# Communication.net
KiCad netlist of a schematic drawn in Altium Designer
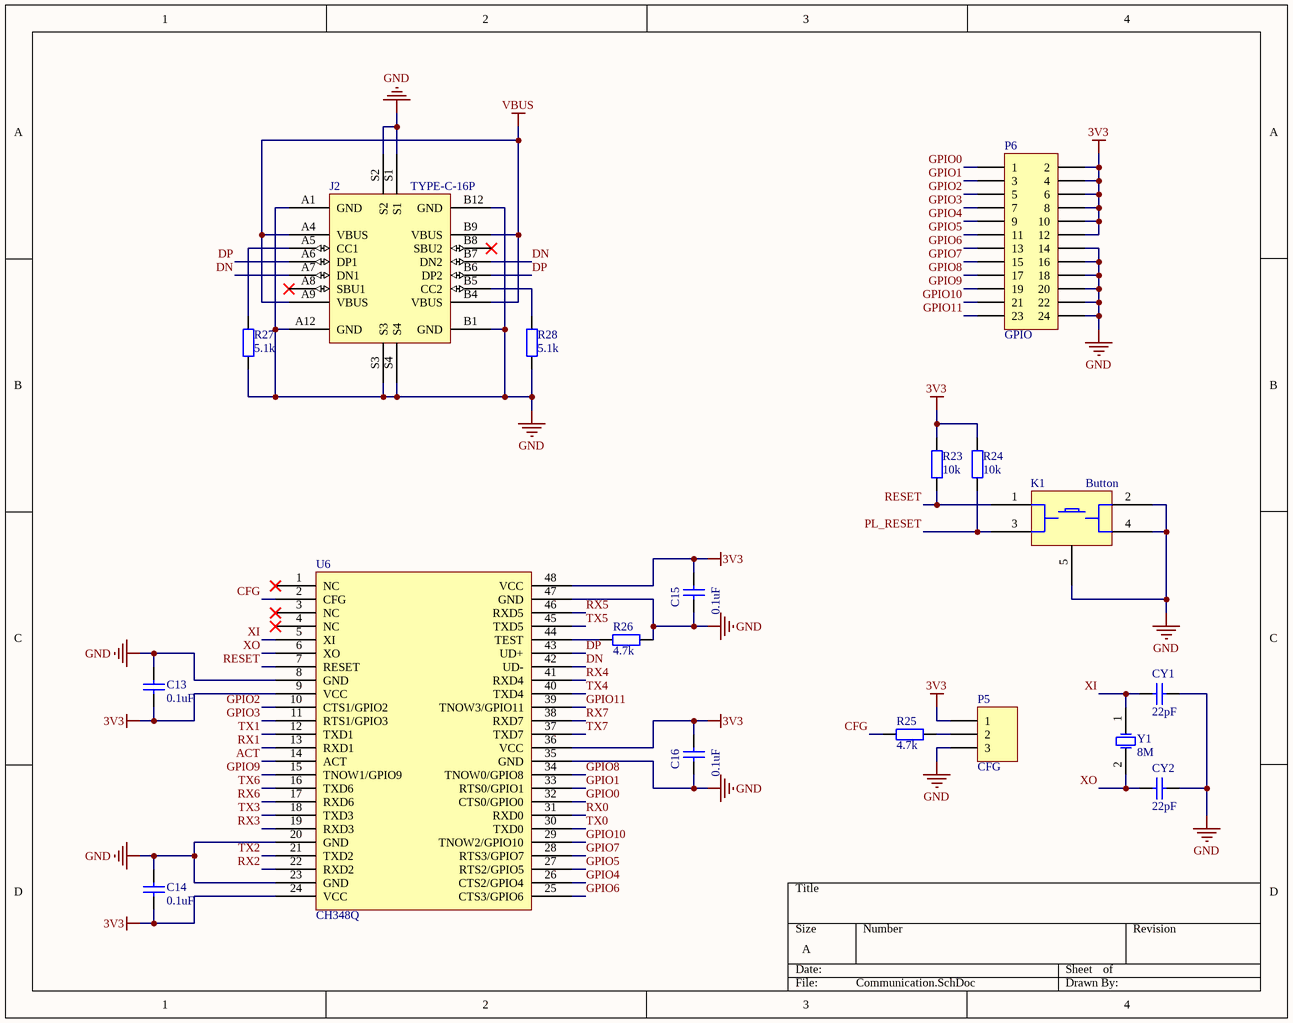
[diagram p0: Communication.SchDoc]

(export (version "E")
  (design (tool "Eeschema 10.0.6"))
  (components
    (comp (ref "C13")
      (value "0.1uF")
      (footprint "CHIP-0603")
      (description "Capacitor")
      (fields (field (name "PUBLISHER") "Altium Limited"))
      (libsource (lib "Miscellaneous Devices") (part "Cap"))
    )
    (comp (ref "C14")
      (value "0.1uF")
      (footprint "CHIP-0603")
      (description "Capacitor")
      (fields (field (name "PUBLISHER") "Altium Limited"))
      (libsource (lib "Miscellaneous Devices") (part "Cap"))
    )
    (comp (ref "C15")
      (value "0.1uF")
      (footprint "CHIP-0603")
      (description "Capacitor")
      (fields (field (name "PUBLISHER") "Altium Limited"))
      (libsource (lib "Miscellaneous Devices") (part "Cap"))
    )
    (comp (ref "C16")
      (value "0.1uF")
      (footprint "CHIP-0603")
      (description "Capacitor")
      (fields (field (name "PUBLISHER") "Altium Limited"))
      (libsource (lib "Miscellaneous Devices") (part "Cap"))
    )
    (comp (ref "CY1")
      (value "22pF")
      (footprint "CHIP-0603")
      (description "Capacitor")
      (fields (field (name "PUBLISHER") "Altium Limited"))
      (libsource (lib "Miscellaneous Devices") (part "Cap"))
    )
    (comp (ref "CY2")
      (value "22pF")
      (footprint "CHIP-0603")
      (description "Capacitor")
      (fields (field (name "PUBLISHER") "Altium Limited"))
      (libsource (lib "Miscellaneous Devices") (part "Cap"))
    )
    (comp (ref "J2")
      (value "TYPE-C-16P")
      (footprint "CONN_KH-TYPE-C_SKE")
      (description "No Description Available")
      (libsource (lib "KH-TYPE-C-16P") (part "KH-TYPE-C-16P"))
    )
    (comp (ref "K1") (value "Button") (footprint "Button") (libsource (lib "Button") (part "Button")))
    (comp (ref "P5")
      (value "CFG")
      (footprint "HDR1X3")
      (description "Header, 3-Pin")
      (fields (field (name "PUBLISHER") "Altium Limited"))
      (libsource (lib "Miscellaneous Connectors") (part "Header 3"))
    )
    (comp (ref "P6")
      (value "GPIO")
      (footprint "HDR2X12")
      (description "Header, 12-Pin, Dual row")
      (fields (field (name "PUBLISHER") "Altium Limited"))
      (libsource (lib "Miscellaneous Connectors") (part "Header 12X2"))
    )
    (comp (ref "R23")
      (value "10k")
      (footprint "CHIP-0603")
      (description "Resistor")
      (fields (field (name "PUBLISHER") "Altium Limited"))
      (libsource (lib "Miscellaneous Devices") (part "Res2"))
    )
    (comp (ref "R24")
      (value "10k")
      (footprint "CHIP-0603")
      (description "Resistor")
      (fields (field (name "PUBLISHER") "Altium Limited"))
      (libsource (lib "Miscellaneous Devices") (part "Res2"))
    )
    (comp (ref "R25")
      (value "4.7k")
      (footprint "CHIP-0603")
      (description "Resistor")
      (fields (field (name "PUBLISHER") "Altium Limited"))
      (libsource (lib "") (part "Res2_1"))
    )
    (comp (ref "R26")
      (value "4.7k")
      (footprint "CHIP-0603")
      (description "Resistor")
      (fields (field (name "PUBLISHER") "Altium Limited"))
      (libsource (lib "") (part "Res2_1"))
    )
    (comp (ref "R27")
      (value "5.1k")
      (footprint "CHIP-0603")
      (description "Resistor")
      (fields (field (name "PUBLISHER") "Altium Limited"))
      (libsource (lib "") (part "Res2_2"))
    )
    (comp (ref "R28")
      (value "5.1k")
      (footprint "CHIP-0603")
      (description "Resistor")
      (fields (field (name "PUBLISHER") "Altium Limited"))
      (libsource (lib "Miscellaneous Devices") (part "Res2"))
    )
    (comp (ref "U6") (value "CH348Q") (footprint "LQFP-48") (libsource (lib "CH348Q") (part "CH348Q")))
    (comp (ref "Y1")
      (value "8M")
      (footprint "S3D12.288000B20F30T")
      (description "Crystal Oscillator")
      (fields (field (name "PUBLISHER") "Altium Limited"))
      (libsource (lib "Miscellaneous Devices") (part "XTAL"))
    )
  )
  (nets
    (net (code "1") (name "/ACT") (class "Default")
      (node (ref "U6") (pin "14") (pinfunction "ACT_14") (pintype "passive"))
    )
    (net (code "2") (name "/CFG") (class "Default")
      (node (ref "R25") (pin "1") (pinfunction "1_1") (pintype "passive"))
      (node (ref "U6") (pin "2") (pinfunction "CFG_2") (pintype "passive"))
    )
    (net (code "3") (name "/DN") (class "Default")
      (node (ref "J2") (pin "A7") (pinfunction "DN1_A7") (pintype "bidirectional"))
      (node (ref "J2") (pin "B7") (pinfunction "DN2_B7") (pintype "bidirectional"))
      (node (ref "U6") (pin "42") (pinfunction "UD-_42") (pintype "passive"))
    )
    (net (code "4") (name "/DP") (class "Default")
      (node (ref "J2") (pin "A6") (pinfunction "DP1_A6") (pintype "bidirectional"))
      (node (ref "J2") (pin "B6") (pinfunction "DP2_B6") (pintype "bidirectional"))
      (node (ref "U6") (pin "43") (pinfunction "UD+_43") (pintype "passive"))
    )
    (net (code "5") (name "/GPIO0") (class "Default")
      (node (ref "P6") (pin "1") (pinfunction "1_1") (pintype "passive"))
      (node (ref "U6") (pin "32") (pinfunction "CTS0/GPIO0_32") (pintype "passive"))
    )
    (net (code "6") (name "/GPIO1") (class "Default")
      (node (ref "P6") (pin "3") (pinfunction "3_3") (pintype "passive"))
      (node (ref "U6") (pin "33") (pinfunction "RTS0/GPIO1_33") (pintype "passive"))
    )
    (net (code "7") (name "/GPIO2") (class "Default")
      (node (ref "P6") (pin "5") (pinfunction "5_5") (pintype "passive"))
      (node (ref "U6") (pin "10") (pinfunction "CTS1/GPIO2_10") (pintype "passive"))
    )
    (net (code "8") (name "/GPIO3") (class "Default")
      (node (ref "P6") (pin "7") (pinfunction "7_7") (pintype "passive"))
      (node (ref "U6") (pin "11") (pinfunction "RTS1/GPIO3_11") (pintype "passive"))
    )
    (net (code "9") (name "/GPIO4") (class "Default")
      (node (ref "P6") (pin "9") (pinfunction "9_9") (pintype "passive"))
      (node (ref "U6") (pin "26") (pinfunction "CTS2/GPIO4_26") (pintype "passive"))
    )
    (net (code "10") (name "/GPIO5") (class "Default")
      (node (ref "P6") (pin "11") (pinfunction "11_11") (pintype "passive"))
      (node (ref "U6") (pin "27") (pinfunction "RTS2/GPIO5_27") (pintype "passive"))
    )
    (net (code "11") (name "/GPIO6") (class "Default")
      (node (ref "P6") (pin "13") (pinfunction "13_13") (pintype "passive"))
      (node (ref "U6") (pin "25") (pinfunction "CTS3/GPIO6_25") (pintype "passive"))
    )
    (net (code "12") (name "/GPIO7") (class "Default")
      (node (ref "P6") (pin "15") (pinfunction "15_15") (pintype "passive"))
      (node (ref "U6") (pin "28") (pinfunction "RTS3/GPIO7_28") (pintype "passive"))
    )
    (net (code "13") (name "/GPIO8") (class "Default")
      (node (ref "P6") (pin "17") (pinfunction "17_17") (pintype "passive"))
      (node (ref "U6") (pin "34") (pinfunction "TNOW0/GPIO8_34") (pintype "passive"))
    )
    (net (code "14") (name "/GPIO9") (class "Default")
      (node (ref "P6") (pin "19") (pinfunction "19_19") (pintype "passive"))
      (node (ref "U6") (pin "15") (pinfunction "TNOW1/GPIO9_15") (pintype "passive"))
    )
    (net (code "15") (name "/GPIO10") (class "Default")
      (node (ref "P6") (pin "21") (pinfunction "21_21") (pintype "passive"))
      (node (ref "U6") (pin "29") (pinfunction "TNOW2/GPIO10_29") (pintype "passive"))
    )
    (net (code "16") (name "/GPIO11") (class "Default")
      (node (ref "P6") (pin "23") (pinfunction "23_23") (pintype "passive"))
      (node (ref "U6") (pin "39") (pinfunction "TNOW3/GPIO11_39") (pintype "passive"))
    )
    (net (code "17") (name "/PL_RESET") (class "Default")
      (node (ref "K1") (pin "3") (pinfunction "A_3") (pintype "passive"))
      (node (ref "R24") (pin "2") (pinfunction "2_2") (pintype "passive"))
    )
    (net (code "18") (name "/RESET") (class "Default")
      (node (ref "K1") (pin "1") (pinfunction "A_1") (pintype "passive"))
      (node (ref "R23") (pin "2") (pinfunction "2_2") (pintype "passive"))
      (node (ref "U6") (pin "7") (pinfunction "RESET_7") (pintype "passive"))
    )
    (net (code "19") (name "/RX0") (class "Default")
      (node (ref "U6") (pin "31") (pinfunction "RXD0_31") (pintype "passive"))
    )
    (net (code "20") (name "/RX1") (class "Default")
      (node (ref "U6") (pin "13") (pinfunction "RXD1_13") (pintype "passive"))
    )
    (net (code "21") (name "/RX2") (class "Default")
      (node (ref "U6") (pin "22") (pinfunction "RXD2_22") (pintype "passive"))
    )
    (net (code "22") (name "/RX3") (class "Default")
      (node (ref "U6") (pin "19") (pinfunction "RXD3_19") (pintype "passive"))
    )
    (net (code "23") (name "/RX4") (class "Default")
      (node (ref "U6") (pin "41") (pinfunction "RXD4_41") (pintype "passive"))
    )
    (net (code "24") (name "/RX5") (class "Default")
      (node (ref "U6") (pin "46") (pinfunction "RXD5_46") (pintype "passive"))
    )
    (net (code "25") (name "/RX6") (class "Default")
      (node (ref "U6") (pin "17") (pinfunction "RXD6_17") (pintype "passive"))
    )
    (net (code "26") (name "/RX7") (class "Default")
      (node (ref "U6") (pin "38") (pinfunction "RXD7_38") (pintype "passive"))
    )
    (net (code "27") (name "/TX0") (class "Default")
      (node (ref "U6") (pin "30") (pinfunction "TXD0_30") (pintype "passive"))
    )
    (net (code "28") (name "/TX1") (class "Default")
      (node (ref "U6") (pin "12") (pinfunction "TXD1_12") (pintype "passive"))
    )
    (net (code "29") (name "/TX2") (class "Default")
      (node (ref "U6") (pin "21") (pinfunction "TXD2_21") (pintype "passive"))
    )
    (net (code "30") (name "/TX3") (class "Default")
      (node (ref "U6") (pin "18") (pinfunction "TXD3_18") (pintype "passive"))
    )
    (net (code "31") (name "/TX4") (class "Default")
      (node (ref "U6") (pin "40") (pinfunction "TXD4_40") (pintype "passive"))
    )
    (net (code "32") (name "/TX5") (class "Default")
      (node (ref "U6") (pin "45") (pinfunction "TXD5_45") (pintype "passive"))
    )
    (net (code "33") (name "/TX6") (class "Default")
      (node (ref "U6") (pin "16") (pinfunction "TXD6_16") (pintype "passive"))
    )
    (net (code "34") (name "/TX7") (class "Default")
      (node (ref "U6") (pin "37") (pinfunction "TXD7_37") (pintype "passive"))
    )
    (net (code "35") (name "/XI") (class "Default")
      (node (ref "CY1") (pin "2") (pinfunction "2_2") (pintype "passive"))
      (node (ref "U6") (pin "5") (pinfunction "XI_5") (pintype "passive"))
      (node (ref "Y1") (pin "1") (pinfunction "OSC1_1") (pintype "passive"))
    )
    (net (code "36") (name "/XO") (class "Default")
      (node (ref "CY2") (pin "2") (pinfunction "2_2") (pintype "passive"))
      (node (ref "U6") (pin "6") (pinfunction "XO_6") (pintype "passive"))
      (node (ref "Y1") (pin "2") (pinfunction "OSC2_2") (pintype "passive"))
    )
    (net (code "37") (name "3V3") (class "Default")
      (node (ref "C13") (pin "2") (pinfunction "2_2") (pintype "passive"))
      (node (ref "C14") (pin "2") (pinfunction "2_2") (pintype "passive"))
      (node (ref "C15") (pin "2") (pinfunction "2_2") (pintype "passive"))
      (node (ref "C16") (pin "2") (pinfunction "2_2") (pintype "passive"))
      (node (ref "P5") (pin "1") (pinfunction "1_1") (pintype "passive"))
      (node (ref "P6") (pin "10") (pinfunction "10_10") (pintype "passive"))
      (node (ref "P6") (pin "12") (pinfunction "12_12") (pintype "passive"))
      (node (ref "P6") (pin "2") (pinfunction "2_2") (pintype "passive"))
      (node (ref "P6") (pin "4") (pinfunction "4_4") (pintype "passive"))
      (node (ref "P6") (pin "6") (pinfunction "6_6") (pintype "passive"))
      (node (ref "P6") (pin "8") (pinfunction "8_8") (pintype "passive"))
      (node (ref "R23") (pin "1") (pinfunction "1_1") (pintype "passive"))
      (node (ref "R24") (pin "1") (pinfunction "1_1") (pintype "passive"))
      (node (ref "U6") (pin "24") (pinfunction "VCC_24") (pintype "passive"))
      (node (ref "U6") (pin "36") (pinfunction "VCC_36") (pintype "passive"))
      (node (ref "U6") (pin "48") (pinfunction "VCC_48") (pintype "passive"))
      (node (ref "U6") (pin "9") (pinfunction "VCC_9") (pintype "passive"))
    )
    (net (code "38") (name "GND") (class "Default")
      (node (ref "C13") (pin "1") (pinfunction "1_1") (pintype "passive"))
      (node (ref "C14") (pin "1") (pinfunction "1_1") (pintype "passive"))
      (node (ref "C15") (pin "1") (pinfunction "1_1") (pintype "passive"))
      (node (ref "C16") (pin "1") (pinfunction "1_1") (pintype "passive"))
      (node (ref "CY1") (pin "1") (pinfunction "1_1") (pintype "passive"))
      (node (ref "CY2") (pin "1") (pinfunction "1_1") (pintype "passive"))
      (node (ref "J2") (pin "A1") (pinfunction "GND_A1") (pintype "power_in"))
      (node (ref "J2") (pin "A12") (pinfunction "GND_A12") (pintype "power_in"))
      (node (ref "J2") (pin "B1") (pinfunction "GND_B1") (pintype "power_in"))
      (node (ref "J2") (pin "B12") (pinfunction "GND_B12") (pintype "power_in"))
      (node (ref "J2") (pin "S1") (pinfunction "S1_S1") (pintype "power_in"))
      (node (ref "J2") (pin "S2") (pinfunction "S2_S2") (pintype "power_in"))
      (node (ref "J2") (pin "S3") (pinfunction "S3_S3") (pintype "power_in"))
      (node (ref "J2") (pin "S4") (pinfunction "S4_S4") (pintype "power_in"))
      (node (ref "K1") (pin "2") (pinfunction "B_2") (pintype "passive"))
      (node (ref "K1") (pin "4") (pinfunction "B_4") (pintype "passive"))
      (node (ref "K1") (pin "5") (pinfunction "Shell_5") (pintype "passive"))
      (node (ref "P5") (pin "3") (pinfunction "3_3") (pintype "passive"))
      (node (ref "P6") (pin "14") (pinfunction "14_14") (pintype "passive"))
      (node (ref "P6") (pin "16") (pinfunction "16_16") (pintype "passive"))
      (node (ref "P6") (pin "18") (pinfunction "18_18") (pintype "passive"))
      (node (ref "P6") (pin "20") (pinfunction "20_20") (pintype "passive"))
      (node (ref "P6") (pin "22") (pinfunction "22_22") (pintype "passive"))
      (node (ref "P6") (pin "24") (pinfunction "24_24") (pintype "passive"))
      (node (ref "R26") (pin "2") (pinfunction "2_2") (pintype "passive"))
      (node (ref "R27") (pin "1") (pinfunction "1_1") (pintype "passive"))
      (node (ref "R28") (pin "2") (pinfunction "2_2") (pintype "passive"))
      (node (ref "U6") (pin "20") (pinfunction "GND_20") (pintype "passive"))
      (node (ref "U6") (pin "23") (pinfunction "GND_23") (pintype "passive"))
      (node (ref "U6") (pin "35") (pinfunction "GND_35") (pintype "passive"))
      (node (ref "U6") (pin "47") (pinfunction "GND_47") (pintype "passive"))
      (node (ref "U6") (pin "8") (pinfunction "GND_8") (pintype "passive"))
    )
    (net (code "39") (name "Net-(J2-CC1)") (class "Default")
      (node (ref "J2") (pin "A5") (pinfunction "CC1_A5") (pintype "bidirectional"))
      (node (ref "R27") (pin "2") (pinfunction "2_2") (pintype "passive"))
    )
    (net (code "40") (name "Net-(J2-CC2)") (class "Default")
      (node (ref "J2") (pin "B5") (pinfunction "CC2_B5") (pintype "bidirectional"))
      (node (ref "R28") (pin "1") (pinfunction "1_1") (pintype "passive"))
    )
    (net (code "41") (name "Net-(P5-Pad2)") (class "Default")
      (node (ref "P5") (pin "2") (pinfunction "2_2") (pintype "passive"))
      (node (ref "R25") (pin "2") (pinfunction "2_2") (pintype "passive"))
    )
    (net (code "42") (name "Net-(U6-TEST)") (class "Default")
      (node (ref "R26") (pin "1") (pinfunction "1_1") (pintype "passive"))
      (node (ref "U6") (pin "44") (pinfunction "TEST_44") (pintype "passive"))
    )
    (net (code "43") (name "VBUS") (class "Default")
      (node (ref "J2") (pin "A4") (pinfunction "VBUS_A4") (pintype "power_in"))
      (node (ref "J2") (pin "A9") (pinfunction "VBUS_A9") (pintype "power_in"))
      (node (ref "J2") (pin "B4") (pinfunction "VBUS_B4") (pintype "power_in"))
      (node (ref "J2") (pin "B9") (pinfunction "VBUS_B9") (pintype "power_in"))
    )
    (net (code "44") (name "unconnected-(J2-SBU1-PadA8)") (class "Default")
      (node (ref "J2") (pin "A8") (pinfunction "SBU1_A8") (pintype "bidirectional+no_connect"))
    )
    (net (code "45") (name "unconnected-(J2-SBU2-PadB8)") (class "Default")
      (node (ref "J2") (pin "B8") (pinfunction "SBU2_B8") (pintype "bidirectional+no_connect"))
    )
    (net (code "46") (name "unconnected-(U6-NC-Pad1)") (class "Default")
      (node (ref "U6") (pin "1") (pinfunction "NC_1") (pintype "passive+no_connect"))
    )
    (net (code "47") (name "unconnected-(U6-NC-Pad3)") (class "Default")
      (node (ref "U6") (pin "3") (pinfunction "NC_3") (pintype "passive+no_connect"))
    )
    (net (code "48") (name "unconnected-(U6-NC-Pad4)") (class "Default")
      (node (ref "U6") (pin "4") (pinfunction "NC_4") (pintype "passive+no_connect"))
    )
  )
)
